# Sheet1.net
KiCad netlist of a schematic drawn in Altium Designer
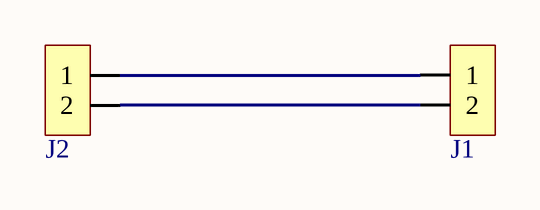
[diagram p0: Sheet1.SchDoc]

(export (version "E")
  (design (tool "Eeschema 10.0.6"))
  (components
    (comp (ref "J1")
      (value "Header Pins")
      (footprint "HEADER PIN 1x2")
      (libsource (lib "ACR Components") (part "Header Pins 1x2"))
    )
    (comp (ref "J2")
      (value "Header Pins")
      (footprint "HEADER PIN 1x2")
      (libsource (lib "") (part "Header Pins 1x2_1"))
    )
  )
  (nets
    (net (code "1") (name "Net-(J1-Pad1)") (class "Default")
      (node (ref "J1") (pin "1") (pinfunction "1_1") (pintype "passive"))
      (node (ref "J2") (pin "1") (pinfunction "1_1") (pintype "passive"))
    )
    (net (code "2") (name "Net-(J1-Pad2)") (class "Default")
      (node (ref "J1") (pin "2") (pinfunction "2_2") (pintype "passive"))
      (node (ref "J2") (pin "2") (pinfunction "2_2") (pintype "passive"))
    )
  )
)
